# 03_-_GPS-SL871-Module-V1_1.net
KiCad netlist of a schematic drawn in Altium Designer
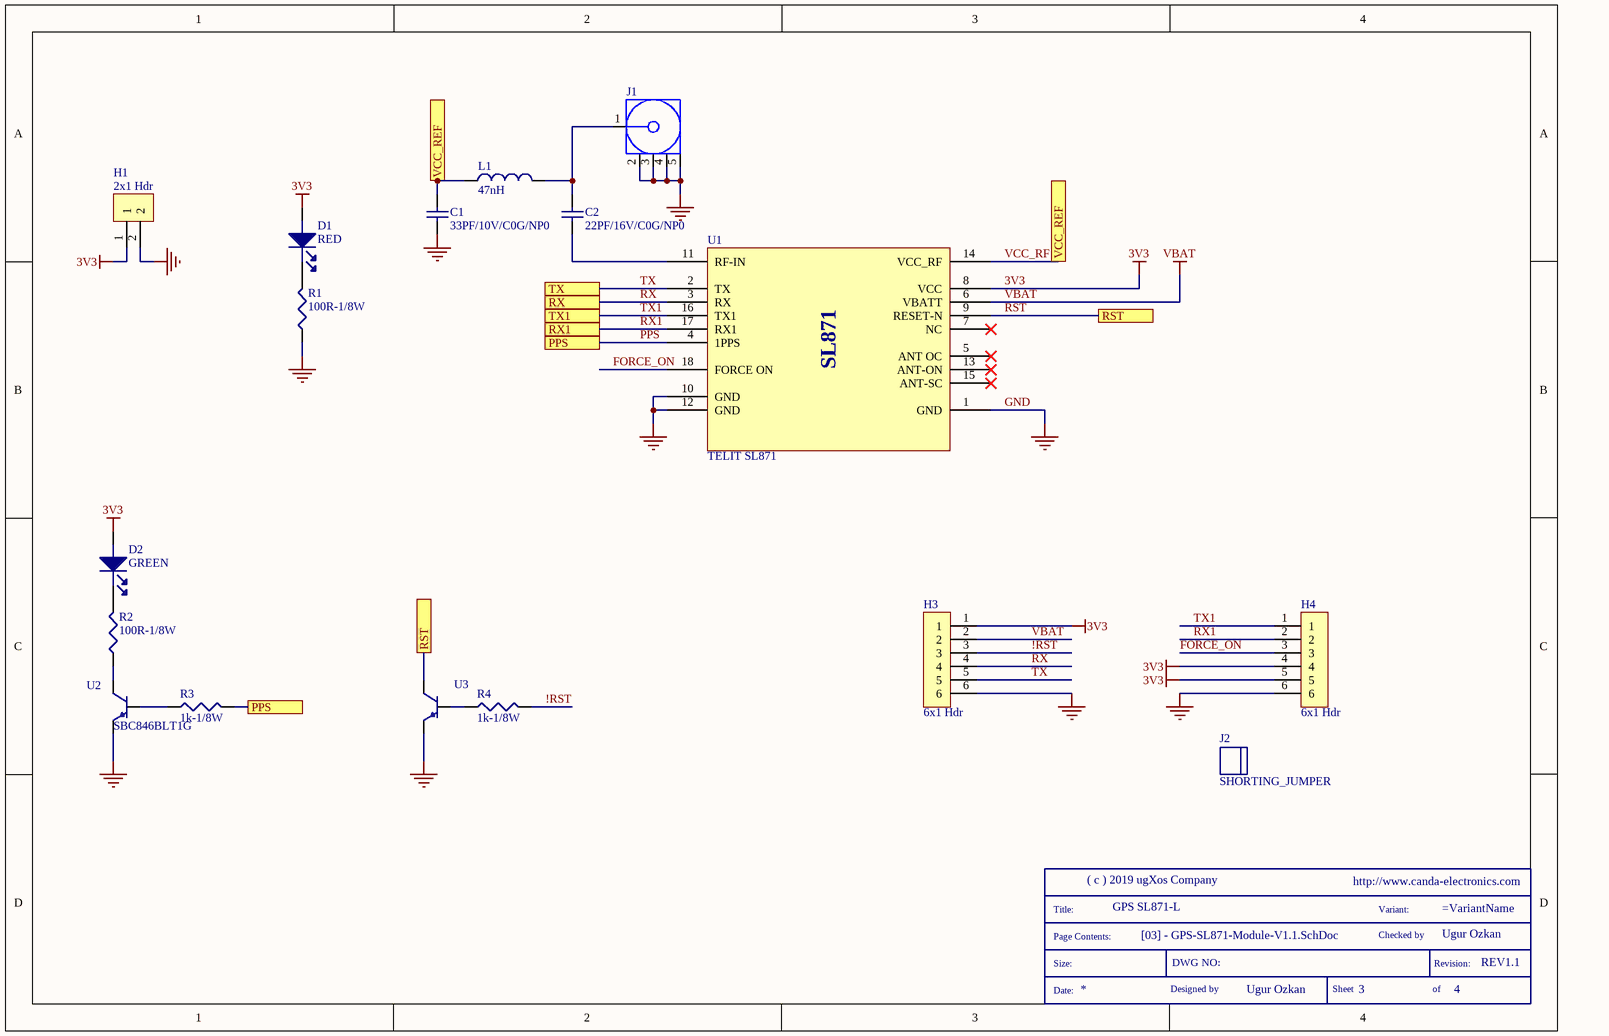
[diagram p0: [03] - GPS-SL871-Module-V1.1.SchDoc]

(export (version "E")
  (design (tool "Eeschema 10.0.6"))
  (components
    (comp (ref "C1")
      (value "33PF/10V/C0G/NP0")
      (footprint "CAP0805")
      (description "CAP CER 33PF 10V C0G/NP0 0805")
      (fields
        (field (name "MANUFACTURER") "Wurth Electronics")
        (field (name "MANUFACTURER PART NUMBER") "885012007003")
      )
      (libsource (lib "ugXos_Library") (part "885012007003"))
    )
    (comp (ref "C2")
      (value "22PF/16V/C0G/NP0")
      (footprint "CAP0805")
      (description "CAP CER 22PF 16V C0G/NP0 0805")
      (fields
        (field (name "MANUFACTURER") "Wurth Electronics")
        (field (name "MANUFACTURER PART NUMBER") "885012007012")
      )
      (libsource (lib "ugXos_Library") (part "885012007012"))
    )
    (comp (ref "D1")
      (value "RED")
      (footprint "LED_0805")
      (description "LED, 0805, RED, 150MCD, 625NM")
      (fields
        (field (name "MANUFACTURER") "Wurth Electronics")
        (field (name "MANUFACTURER PART NUMBER") "150080RS75000")
      )
      (libsource (lib "ugXos_Library") (part "150080RS75000"))
    )
    (comp (ref "D2")
      (value "GREEN")
      (footprint "LED_0805")
      (description "LED, 0805, B GREEN, 40MCD, 570NM")
      (fields
        (field (name "MANUFACTURER") "Wurth Electronics")
        (field (name "MANUFACTURER PART NUMBER") "150080VS75000")
      )
      (libsource (lib "ugXos_Library") (part "150080VS75000"))
    )
    (comp (ref "H1")
      (value "2x1 Hdr")
      (footprint "Hdr_Male_1x2_2.54mm")
      (description "Connector, Vertical, Through Hole, Header, 2, 2.54 Mm")
      (fields
        (field (name "MANUFACTURER") "Wurth Electronics")
        (field (name "MANUFACTURER PART NUMBER") "61300211121")
      )
      (libsource (lib "ugXos_Library") (part "61300211121"))
    )
    (comp (ref "H3")
      (value "6x1 Hdr")
      (footprint "Hdr_Female_1x6_2.54mm")
      (description "Connector, Vertical, Through Hole, Header 6, 2.54 Mm")
      (fields
        (field (name "MANUFACTURER") "Wurth Electronics")
        (field (name "MANUFACTURER PART NUMBER") "61300611121")
      )
      (libsource (lib "ugXos_Library") (part "61300611121"))
    )
    (comp (ref "H4")
      (value "6x1 Hdr")
      (footprint "Hdr_Female_1x6_2.54mm")
      (description "Connector, Vertical, Through Hole, Header 6, 2.54 Mm")
      (fields
        (field (name "MANUFACTURER") "Wurth Electronics")
        (field (name "MANUFACTURER PART NUMBER") "61300611121")
      )
      (libsource (lib "") (part "61300611121_1"))
    )
    (comp (ref "J1")
      (value "WR-SMA-THT")
      (footprint "WR_SMA_THT_60311002114501")
      (description "WR-SMA SMA PCB THT Jack Right Angle")
      (fields
        (field (name "PART NUMBER") "60311002114501")
        (field (name "MANUFACTURER") "Wurth Electronics")
        (field (name "PUBLISHER") "Wurth Elektronik")
      )
      (libsource (lib "ugXos_Library") (part "60311002114501"))
    )
    (comp (ref "J2") (value "SHORTING_JUMPER") (libsource (lib "ugXos_Library") (part "SHORTING_JUMPER")))
    (comp (ref "L1")
      (value "47nH")
      (footprint "L0805")
      (description "IND 0805")
      (libsource (lib "ugXos_Library") (part "IND_0805"))
    )
    (comp (ref "R1")
      (value "100R-1/8W")
      (footprint "R0805")
      (description "RES SMD 100 OHM 0.1% 1/8W 0805")
      (fields
        (field (name "MANUFACTURER") "Panasonic")
        (field (name "MANUFACTURER PART NUMBER") "ERA6AEB101V")
      )
      (libsource (lib "ugXos_Library") (part "ERA6AEB101V"))
    )
    (comp (ref "R2")
      (value "100R-1/8W")
      (footprint "R0805")
      (description "RES SMD 100 OHM 0.1% 1/8W 0805")
      (fields
        (field (name "MANUFACTURER") "Panasonic")
        (field (name "MANUFACTURER PART NUMBER") "ERA6AEB101V")
      )
      (libsource (lib "ugXos_Library") (part "ERA6AEB101V"))
    )
    (comp (ref "R3")
      (value "1k-1/8W")
      (footprint "R0805")
      (description "Res Thin Film 0805 1K Ohm 0.5% 0.125W(1/8W) ±25ppm/C Molded SMD Automotive Punched T/R")
      (fields
        (field (name "MANUFACTURER") "Panasonic")
        (field (name "MANUFACTURER PART NUMBER") "ERA-6AED102V")
      )
      (libsource (lib "ugXos_Library") (part "ERA-6AED102V"))
    )
    (comp (ref "R4")
      (value "1k-1/8W")
      (footprint "R0805")
      (description "Res Thin Film 0805 1K Ohm 0.5% 0.125W(1/8W) ±25ppm/C Molded SMD Automotive Punched T/R")
      (fields
        (field (name "MANUFACTURER") "Panasonic")
        (field (name "MANUFACTURER PART NUMBER") "ERA-6AED102V")
      )
      (libsource (lib "ugXos_Library") (part "ERA-6AED102V"))
    )
    (comp (ref "U1")
      (value "TELIT SL871")
      (footprint "Telit_SL871")
      (description "Telit GNSS MODULE")
      (fields (field (name "MANUFACTURER") "Telit"))
      (libsource (lib "ugXos_Library") (part "TELIT SL871"))
    )
    (comp (ref "U2")
      (value "SBC846BLT1G")
      (footprint "SOT-23")
      (description "BC846 NPN 65V 0.1A SOT-23")
      (fields (field (name "MANUFACTURER") "ON Semiconductor"))
      (libsource (lib "ugXos_Library") (part "SBC846BLT1G"))
    )
    (comp (ref "U3")
      (value "SBC846BLT1G")
      (footprint "SOT-23")
      (description "BC846 NPN 65V 0.1A SOT-23")
      (fields (field (name "MANUFACTURER") "ON Semiconductor"))
      (libsource (lib "ugXos_Library") (part "SBC846BLT1G"))
    )
  )
  (nets
    (net (code "1") (name "/!RST") (class "Default")
      (node (ref "H3") (pin "3") (pinfunction "3_3") (pintype "passive"))
      (node (ref "R4") (pin "2") (pinfunction "2_2") (pintype "passive"))
    )
    (net (code "2") (name "/FORCE_ON") (class "Default")
      (node (ref "H4") (pin "3") (pinfunction "3_3") (pintype "passive"))
      (node (ref "U1") (pin "18") (pinfunction "FORCE_ON_18") (pintype "passive"))
    )
    (net (code "3") (name "/PPS") (class "Default")
      (node (ref "R3") (pin "2") (pinfunction "2_2") (pintype "passive"))
      (node (ref "U1") (pin "4") (pinfunction "1PPS_4") (pintype "passive"))
    )
    (net (code "4") (name "/RST") (class "Default")
      (node (ref "U1") (pin "9") (pinfunction "RESET-N_9") (pintype "passive"))
      (node (ref "U3") (pin "3") (pinfunction "C_3") (pintype "passive"))
    )
    (net (code "5") (name "/RX") (class "Default")
      (node (ref "H3") (pin "4") (pinfunction "4_4") (pintype "passive"))
      (node (ref "U1") (pin "3") (pinfunction "RX_3") (pintype "passive"))
    )
    (net (code "6") (name "/RX1") (class "Default")
      (node (ref "H4") (pin "2") (pinfunction "2_2") (pintype "passive"))
      (node (ref "U1") (pin "17") (pinfunction "RX1_17") (pintype "passive"))
    )
    (net (code "7") (name "/TX") (class "Default")
      (node (ref "H3") (pin "5") (pinfunction "5_5") (pintype "passive"))
      (node (ref "U1") (pin "2") (pinfunction "TX_2") (pintype "passive"))
    )
    (net (code "8") (name "/TX1") (class "Default")
      (node (ref "H4") (pin "1") (pinfunction "1_1") (pintype "passive"))
      (node (ref "U1") (pin "16") (pinfunction "TX1_16") (pintype "passive"))
    )
    (net (code "9") (name "/VCC_RF") (class "Default")
      (node (ref "C1") (pin "1") (pinfunction "1_1") (pintype "passive"))
      (node (ref "L1") (pin "1") (pinfunction "1_1") (pintype "passive"))
      (node (ref "U1") (pin "14") (pinfunction "VCC_RF_14") (pintype "passive"))
    )
    (net (code "10") (name "3V3") (class "Default")
      (node (ref "D1") (pin "1") (pinfunction "Anode_1") (pintype "passive"))
      (node (ref "D2") (pin "1") (pinfunction "Anode_1") (pintype "passive"))
      (node (ref "H1") (pin "1") (pinfunction "1_1") (pintype "passive"))
      (node (ref "H3") (pin "1") (pinfunction "1_1") (pintype "passive"))
      (node (ref "H4") (pin "4") (pinfunction "4_4") (pintype "passive"))
      (node (ref "H4") (pin "5") (pinfunction "5_5") (pintype "passive"))
      (node (ref "U1") (pin "8") (pinfunction "VCC_8") (pintype "passive"))
    )
    (net (code "11") (name "GND") (class "Default")
      (node (ref "C1") (pin "2") (pinfunction "2_2") (pintype "passive"))
      (node (ref "H1") (pin "2") (pinfunction "2_2") (pintype "passive"))
      (node (ref "H3") (pin "6") (pinfunction "6_6") (pintype "passive"))
      (node (ref "H4") (pin "6") (pinfunction "6_6") (pintype "passive"))
      (node (ref "J1") (pin "2") (pinfunction "GND_2") (pintype "passive"))
      (node (ref "J1") (pin "3") (pinfunction "GND_3") (pintype "passive"))
      (node (ref "J1") (pin "4") (pinfunction "GND_4") (pintype "passive"))
      (node (ref "J1") (pin "5") (pinfunction "GND_5") (pintype "passive"))
      (node (ref "R1") (pin "1") (pinfunction "1_1") (pintype "passive"))
      (node (ref "U1") (pin "1") (pinfunction "GND_1") (pintype "passive"))
      (node (ref "U1") (pin "10") (pinfunction "GND_10") (pintype "passive"))
      (node (ref "U1") (pin "12") (pinfunction "GND_12") (pintype "passive"))
      (node (ref "U2") (pin "2") (pinfunction "E_2") (pintype "passive"))
      (node (ref "U3") (pin "2") (pinfunction "E_2") (pintype "passive"))
    )
    (net (code "12") (name "Net-(D1-Cathode)") (class "Default")
      (node (ref "D1") (pin "2") (pinfunction "Cathode_2") (pintype "passive"))
      (node (ref "R1") (pin "2") (pinfunction "2_2") (pintype "passive"))
    )
    (net (code "13") (name "Net-(D2-Cathode)") (class "Default")
      (node (ref "D2") (pin "2") (pinfunction "Cathode_2") (pintype "passive"))
      (node (ref "R2") (pin "2") (pinfunction "2_2") (pintype "passive"))
    )
    (net (code "14") (name "Net-(J1-Signal)") (class "Default")
      (node (ref "C2") (pin "2") (pinfunction "2_2") (pintype "passive"))
      (node (ref "J1") (pin "1") (pinfunction "Signal_1") (pintype "passive"))
      (node (ref "L1") (pin "2") (pinfunction "2_2") (pintype "passive"))
    )
    (net (code "15") (name "Net-(U1-RF-IN)") (class "Default")
      (node (ref "C2") (pin "1") (pinfunction "1_1") (pintype "passive"))
      (node (ref "U1") (pin "11") (pinfunction "RF-IN_11") (pintype "passive"))
    )
    (net (code "16") (name "Net-(U2-B)") (class "Default")
      (node (ref "R3") (pin "1") (pinfunction "1_1") (pintype "passive"))
      (node (ref "U2") (pin "1") (pinfunction "B_1") (pintype "passive"))
    )
    (net (code "17") (name "Net-(U2-C)") (class "Default")
      (node (ref "R2") (pin "1") (pinfunction "1_1") (pintype "passive"))
      (node (ref "U2") (pin "3") (pinfunction "C_3") (pintype "passive"))
    )
    (net (code "18") (name "Net-(U3-B)") (class "Default")
      (node (ref "R4") (pin "1") (pinfunction "1_1") (pintype "passive"))
      (node (ref "U3") (pin "1") (pinfunction "B_1") (pintype "passive"))
    )
    (net (code "19") (name "VBAT") (class "Default")
      (node (ref "H3") (pin "2") (pinfunction "2_2") (pintype "passive"))
      (node (ref "U1") (pin "6") (pinfunction "VBATT_6") (pintype "passive"))
    )
    (net (code "20") (name "unconnected-(U1-ANT-ON-Pad13)") (class "Default")
      (node (ref "U1") (pin "13") (pinfunction "ANT-ON_13") (pintype "passive+no_connect"))
    )
    (net (code "21") (name "unconnected-(U1-ANT-SC-Pad15)") (class "Default")
      (node (ref "U1") (pin "15") (pinfunction "ANT-SC_15") (pintype "passive+no_connect"))
    )
    (net (code "22") (name "unconnected-(U1-ANT_OC-Pad5)") (class "Default")
      (node (ref "U1") (pin "5") (pinfunction "ANT_OC_5") (pintype "passive+no_connect"))
    )
    (net (code "23") (name "unconnected-(U1-NC-Pad7)") (class "Default")
      (node (ref "U1") (pin "7") (pinfunction "NC_7") (pintype "passive+no_connect"))
    )
  )
)
